# Mach_nap_HEALA.net
KiCad netlist of a schematic drawn in Altium Designer
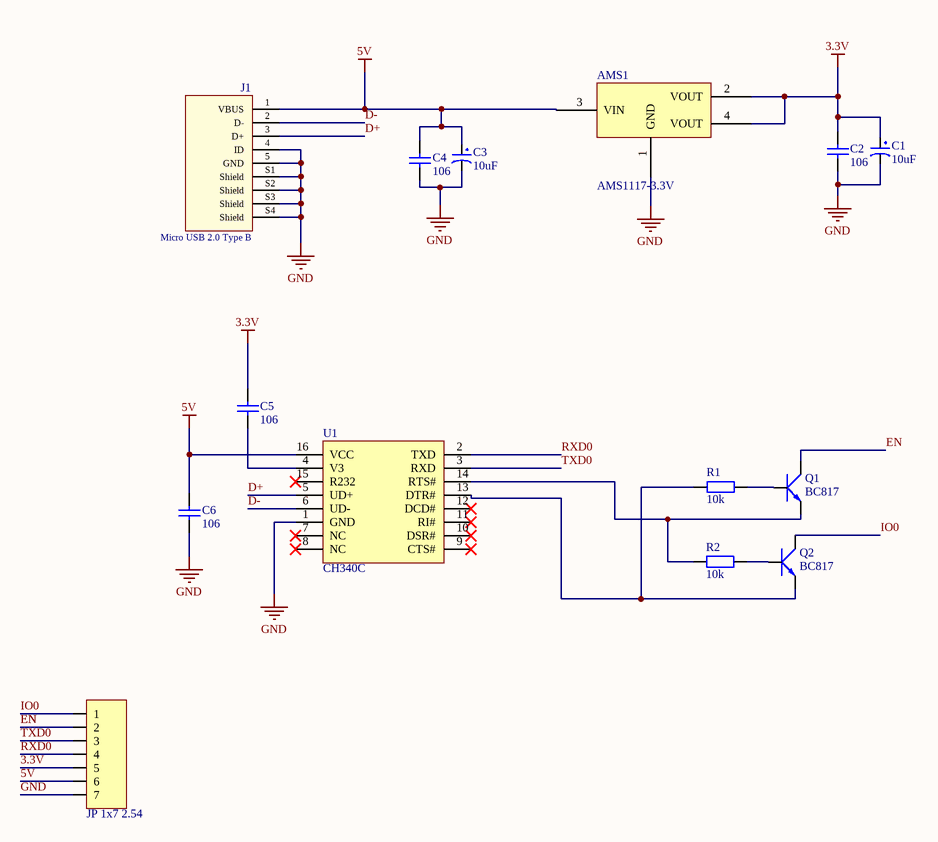
[diagram p0: Mach_nap_HEALA.SchDoc]

(export (version "E")
  (design (tool "Eeschema 10.0.6"))
  (components
    (comp (ref "AMS1")
      (value "AMS1117-3.3V")
      (footprint "SOT223")
      (description "Dán")
      (libsource (lib "IC") (part "AMS1117 SMD"))
    )
    (comp (ref "C1")
      (value "10uF")
      (footprint "tu hoa 4mm")
      (description "Cắm")
      (libsource (lib "Capacitor") (part "Tu Hoa 10uF 25V 4x7"))
    )
    (comp (ref "C2")
      (value "106")
      (footprint "tu 1206")
      (description "Dán")
      (libsource (lib "Capacitor") (part "Tu 1206 106 16V 20%"))
    )
    (comp (ref "C3")
      (value "10uF")
      (footprint "tu hoa 4mm")
      (description "Cắm")
      (libsource (lib "Capacitor") (part "Tu Hoa 10uF 25V 4x7"))
    )
    (comp (ref "C4")
      (value "106")
      (footprint "tu 1206")
      (description "Dán")
      (libsource (lib "Capacitor") (part "Tu 1206 106 16V 20%"))
    )
    (comp (ref "C5")
      (value "106")
      (footprint "tu 1206")
      (description "Dán")
      (libsource (lib "Capacitor") (part "Tu 1206 106 16V 20%"))
    )
    (comp (ref "C6")
      (value "106")
      (footprint "tu 1206")
      (description "Dán")
      (libsource (lib "Capacitor") (part "Tu 1206 106 16V 20%"))
    )
    (comp (ref "J1")
      (value "Micro USB 2.0 Type B")
      (footprint "629105136821")
      (description "Micro USB 2.0 Type B Horizontal SMT 5 Contacts WR-COM")
      (fields (field (name "PART NUMBER") "629105136821") (field (name "PUBLISHER") "Wurth Elektronik"))
      (libsource (lib "USB") (part "629105136821"))
    )
    (comp (ref "JP1")
      (value "JP 1x7 2.54")
      (footprint "JP 1x7 DT")
      (description "Cắm")
      (libsource (lib "Jump") (part "JP 1x7 2.54 Duc Thang"))
    )
    (comp (ref "Q1")
      (value "BC817")
      (footprint "SOT-23")
      (description "SOT-23 - C8658")
      (libsource (lib "TranFet") (part "Trans BC817"))
    )
    (comp (ref "Q2")
      (value "BC817")
      (footprint "SOT-23")
      (description "SOT-23 - C8658")
      (libsource (lib "TranFet") (part "Trans BC817"))
    )
    (comp (ref "R1")
      (value "10k")
      (footprint "tro smd 1206")
      (description "Dán")
      (libsource (lib "Resistor") (part "Tro 1206 5% 10k"))
    )
    (comp (ref "R2")
      (value "10k")
      (footprint "tro smd 1206")
      (description "Dán")
      (libsource (lib "Resistor") (part "Tro 1206 5% 10k"))
    )
    (comp (ref "U1")
      (value "CH340C")
      (footprint "SOIC16_50_284_25X90_SMT")
      (description "USB Bridge, USB to UART USB 2.0 UART Interface")
      (fields (field (name "MANUFACTURER") "Olimex"))
      (libsource (lib "IC") (part "CH340C"))
    )
  )
  (nets
    (net (code "1") (name "/D+") (class "Default")
      (node (ref "J1") (pin "3") (pinfunction "D+_3") (pintype "passive"))
      (node (ref "U1") (pin "5") (pinfunction "UD+_5") (pintype "passive"))
    )
    (net (code "2") (name "/D-") (class "Default")
      (node (ref "J1") (pin "2") (pinfunction "D-_2") (pintype "passive"))
      (node (ref "U1") (pin "6") (pinfunction "UD-_6") (pintype "passive"))
    )
    (net (code "3") (name "/EN") (class "Default")
      (node (ref "JP1") (pin "2") (pinfunction "2_2") (pintype "passive"))
      (node (ref "Q1") (pin "3") (pinfunction "C_3") (pintype "passive"))
    )
    (net (code "4") (name "/IO0") (class "Default")
      (node (ref "JP1") (pin "1") (pinfunction "1_1") (pintype "passive"))
      (node (ref "Q2") (pin "3") (pinfunction "C_3") (pintype "passive"))
    )
    (net (code "5") (name "/RXD0") (class "Default")
      (node (ref "JP1") (pin "4") (pinfunction "4_4") (pintype "passive"))
      (node (ref "U1") (pin "2") (pinfunction "TXD_2") (pintype "passive"))
    )
    (net (code "6") (name "/TXD0") (class "Default")
      (node (ref "JP1") (pin "3") (pinfunction "3_3") (pintype "passive"))
      (node (ref "U1") (pin "3") (pinfunction "RXD_3") (pintype "passive"))
    )
    (net (code "7") (name "3.3V") (class "Default")
      (node (ref "AMS1") (pin "2") (pinfunction "VOUT_2") (pintype "passive"))
      (node (ref "AMS1") (pin "4") (pinfunction "VOUT_4") (pintype "passive"))
      (node (ref "C1") (pin "1") (pinfunction "1_1") (pintype "passive"))
      (node (ref "C2") (pin "1") (pinfunction "1_1") (pintype "passive"))
      (node (ref "C5") (pin "1") (pinfunction "1_1") (pintype "passive"))
      (node (ref "JP1") (pin "5") (pinfunction "5_5") (pintype "passive"))
    )
    (net (code "8") (name "5V") (class "Default")
      (node (ref "AMS1") (pin "3") (pinfunction "VIN_3") (pintype "passive"))
      (node (ref "C3") (pin "1") (pinfunction "1_1") (pintype "passive"))
      (node (ref "C4") (pin "1") (pinfunction "1_1") (pintype "passive"))
      (node (ref "C6") (pin "1") (pinfunction "1_1") (pintype "passive"))
      (node (ref "J1") (pin "1") (pinfunction "VBUS_1") (pintype "passive"))
      (node (ref "JP1") (pin "6") (pinfunction "6_6") (pintype "passive"))
      (node (ref "U1") (pin "16") (pinfunction "VCC_16") (pintype "passive"))
    )
    (net (code "9") (name "GND") (class "Default")
      (node (ref "AMS1") (pin "1") (pinfunction "GND_1") (pintype "passive"))
      (node (ref "C1") (pin "2") (pinfunction "2_2") (pintype "passive"))
      (node (ref "C2") (pin "2") (pinfunction "2_2") (pintype "passive"))
      (node (ref "C3") (pin "2") (pinfunction "2_2") (pintype "passive"))
      (node (ref "C4") (pin "2") (pinfunction "2_2") (pintype "passive"))
      (node (ref "C6") (pin "2") (pinfunction "2_2") (pintype "passive"))
      (node (ref "J1") (pin "4") (pinfunction "ID_4") (pintype "passive"))
      (node (ref "J1") (pin "5") (pinfunction "GND_5") (pintype "passive"))
      (node (ref "J1") (pin "S1") (pinfunction "Shield_S1") (pintype "passive"))
      (node (ref "J1") (pin "S2") (pinfunction "Shield_S2") (pintype "passive"))
      (node (ref "J1") (pin "S3") (pinfunction "Shield_S3") (pintype "passive"))
      (node (ref "J1") (pin "S4") (pinfunction "Shield_S4") (pintype "passive"))
      (node (ref "JP1") (pin "7") (pinfunction "7_7") (pintype "passive"))
      (node (ref "U1") (pin "1") (pinfunction "GND_1") (pintype "passive"))
    )
    (net (code "10") (name "Net-(Q1-B)") (class "Default")
      (node (ref "Q1") (pin "1") (pinfunction "B_1") (pintype "passive"))
      (node (ref "R1") (pin "2") (pinfunction "2_2") (pintype "passive"))
    )
    (net (code "11") (name "Net-(Q1-E)") (class "Default")
      (node (ref "Q1") (pin "2") (pinfunction "E_2") (pintype "passive"))
      (node (ref "R2") (pin "1") (pinfunction "1_1") (pintype "passive"))
      (node (ref "U1") (pin "14") (pinfunction "RTS#_14") (pintype "passive"))
    )
    (net (code "12") (name "Net-(Q2-B)") (class "Default")
      (node (ref "Q2") (pin "1") (pinfunction "B_1") (pintype "passive"))
      (node (ref "R2") (pin "2") (pinfunction "2_2") (pintype "passive"))
    )
    (net (code "13") (name "Net-(Q2-E)") (class "Default")
      (node (ref "Q2") (pin "2") (pinfunction "E_2") (pintype "passive"))
      (node (ref "U1") (pin "13") (pinfunction "DTR#_13") (pintype "passive"))
    )
    (net (code "14") (name "Net-(U1-V3)") (class "Default")
      (node (ref "C5") (pin "2") (pinfunction "2_2") (pintype "passive"))
      (node (ref "U1") (pin "4") (pinfunction "V3_4") (pintype "passive"))
    )
    (net (code "15") (name "unconnected-(R1-Pad1)") (class "Default")
      (node (ref "R1") (pin "1") (pinfunction "1_1") (pintype "passive"))
    )
    (net (code "16") (name "unconnected-(U1-CTS#-Pad9)") (class "Default")
      (node (ref "U1") (pin "9") (pinfunction "CTS#_9") (pintype "passive+no_connect"))
    )
    (net (code "17") (name "unconnected-(U1-DCD#-Pad12)") (class "Default")
      (node (ref "U1") (pin "12") (pinfunction "DCD#_12") (pintype "passive+no_connect"))
    )
    (net (code "18") (name "unconnected-(U1-DSR#-Pad10)") (class "Default")
      (node (ref "U1") (pin "10") (pinfunction "DSR#_10") (pintype "passive+no_connect"))
    )
    (net (code "19") (name "unconnected-(U1-NC-Pad7)") (class "Default")
      (node (ref "U1") (pin "7") (pinfunction "NC_7") (pintype "passive+no_connect"))
    )
    (net (code "20") (name "unconnected-(U1-NC-Pad8)") (class "Default")
      (node (ref "U1") (pin "8") (pinfunction "NC_8") (pintype "passive+no_connect"))
    )
    (net (code "21") (name "unconnected-(U1-R232-Pad15)") (class "Default")
      (node (ref "U1") (pin "15") (pinfunction "R232_15") (pintype "passive+no_connect"))
    )
    (net (code "22") (name "unconnected-(U1-RI#-Pad11)") (class "Default")
      (node (ref "U1") (pin "11") (pinfunction "RI#_11") (pintype "passive+no_connect"))
    )
  )
)
